# FPGA.net
KiCad netlist of a schematic drawn in Altium Designer
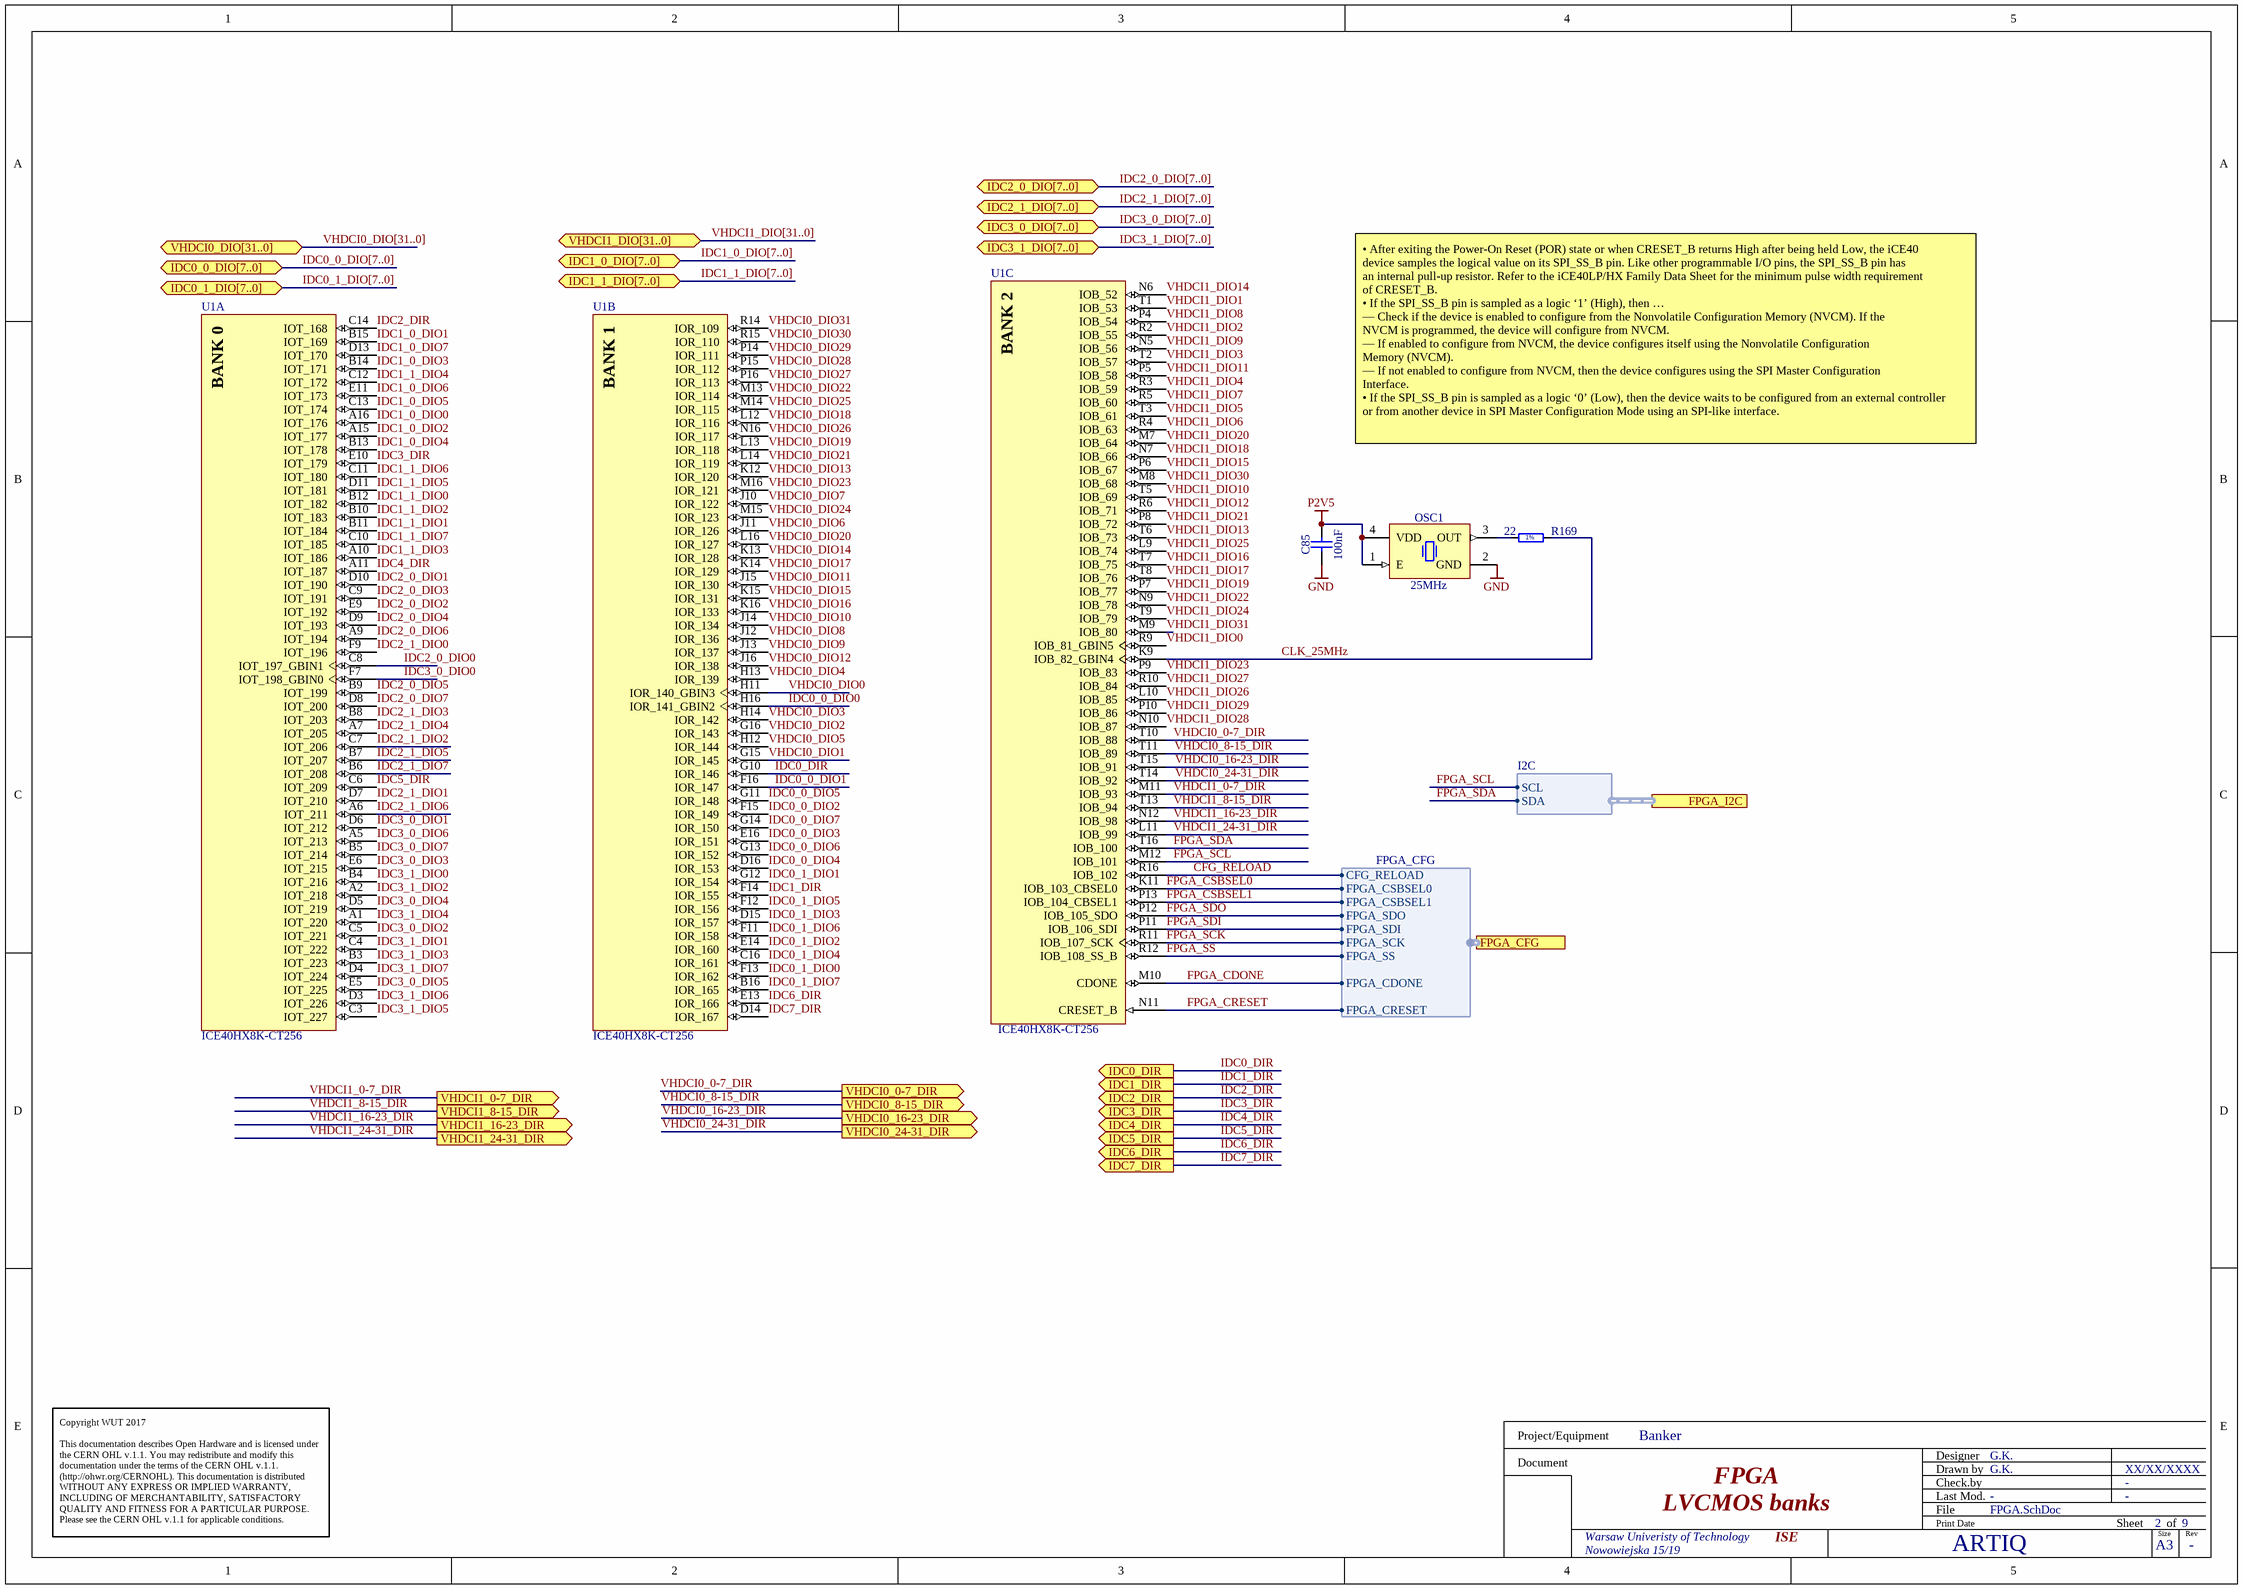
[diagram p0: FPGA.SchDoc]

(export (version "E")
  (design (tool "Eeschema 10.0.6"))
  (components
    (comp (ref "C85")
      (value "100nF")
      (footprint "CAPC1005X55N")
      (description "Non-polarised capacitor")
      (fields
        (field (name "PART NUMBER") "CC0402_100NF_16V_10%_X5R")
        (field (name "VOLTAGE") "16V")
        (field (name "AUTHOR") "CERN DEM JLC")
      )
      (libsource (lib "Capacitors") (part "Capacitor - non polarized"))
    )
    (comp (ref "OSC1")
      (value "25MHz")
      (footprint "OSC_ECS_ECS-3525")
      (description "Oscillator 4 pins 1=E/D 2=GND 3=OUT 4=VDD")
      (fields
        (field (name "PART NUMBER") "OSC_25MHZ_ECS_ECS-3525-250-B")
        (field (name "MANUFACTURER") "ECS")
        (field (name "AUTHOR") "CERN DEM JLC")
      )
      (libsource (lib "ICs And Semiconductors") (part "Oscillator 1E 2GND 3OUT 4VDD"))
    )
    (comp (ref "R169")
      (value "22")
      (footprint "RESC1005X40N")
      (description "Resistor - 1%")
      (fields
        (field (name "PART NUMBER") "R0402_22R_1%_0.0625W_100PPM")
        (field (name "POWER") "0.0625W")
        (field (name "AUTHOR") "CERN DEM JLC")
      )
      (libsource (lib "Resistors") (part "Resistor - 1%"))
    )
    (comp (ref "U1")
      (value "ICE40HX8K-CT256")
      (footprint "LATC-caBGA-256")
      (fields (field (name "MANUFACTURER") "Lattice Semiconductor"))
      (libsource (lib "Altium Content Vault") (part "LATC-HX8K-caBGA-256"))
    )
  )
  (nets
    (net (code "3") (name "/CFG_RELOAD") (class "Default")
      (node (ref "U1") (pin "R16") (pinfunction "IOB_102_R16") (pintype "bidirectional"))
    )
    (net (code "4") (name "/CLK_25MHz") (class "Default")
      (node (ref "R169") (pin "2") (pinfunction "2_2") (pintype "passive"))
      (node (ref "U1") (pin "K9") (pinfunction "IOB_82_GBIN4_K9") (pintype "bidirectional"))
    )
    (net (code "5") (name "/FPGA_CDONE") (class "Default")
      (node (ref "U1") (pin "M10") (pinfunction "CDONE_M10") (pintype "bidirectional"))
    )
    (net (code "6") (name "/FPGA_CRESET") (class "Default")
      (node (ref "U1") (pin "N11") (pinfunction "CRESET_B_N11") (pintype "input"))
    )
    (net (code "7") (name "/FPGA_CSBSEL0") (class "Default")
      (node (ref "U1") (pin "K11") (pinfunction "IOB_103_CBSEL0_K11") (pintype "bidirectional"))
    )
    (net (code "8") (name "/FPGA_CSBSEL1") (class "Default")
      (node (ref "U1") (pin "P13") (pinfunction "IOB_104_CBSEL1_P13") (pintype "bidirectional"))
    )
    (net (code "9") (name "/FPGA_SCK") (class "Default")
      (node (ref "U1") (pin "R11") (pinfunction "IOB_107_SCK_R11") (pintype "bidirectional"))
    )
    (net (code "10") (name "/FPGA_SCL") (class "Default")
      (node (ref "U1") (pin "M12") (pinfunction "IOB_101_M12") (pintype "bidirectional"))
    )
    (net (code "11") (name "/FPGA_SDA") (class "Default")
      (node (ref "U1") (pin "T16") (pinfunction "IOB_100_T16") (pintype "bidirectional"))
    )
    (net (code "12") (name "/FPGA_SDI") (class "Default")
      (node (ref "U1") (pin "P11") (pinfunction "IOB_106_SDI_P11") (pintype "bidirectional"))
    )
    (net (code "13") (name "/FPGA_SDO") (class "Default")
      (node (ref "U1") (pin "P12") (pinfunction "IOB_105_SDO_P12") (pintype "bidirectional"))
    )
    (net (code "14") (name "/FPGA_SS") (class "Default")
      (node (ref "U1") (pin "R12") (pinfunction "IOB_108_SS_B_R12") (pintype "bidirectional"))
    )
    (net (code "15") (name "/IDC0_0_DIO0") (class "Default")
      (node (ref "U1") (pin "H16") (pinfunction "IOR_141_GBIN2_H16") (pintype "bidirectional"))
    )
    (net (code "16") (name "/IDC0_0_DIO1") (class "Default")
      (node (ref "U1") (pin "F16") (pinfunction "IOR_147_F16") (pintype "bidirectional"))
    )
    (net (code "17") (name "/IDC0_0_DIO2") (class "Default")
      (node (ref "U1") (pin "F15") (pinfunction "IOR_149_F15") (pintype "bidirectional"))
    )
    (net (code "18") (name "/IDC0_0_DIO3") (class "Default")
      (node (ref "U1") (pin "E16") (pinfunction "IOR_151_E16") (pintype "bidirectional"))
    )
    (net (code "19") (name "/IDC0_0_DIO4") (class "Default")
      (node (ref "U1") (pin "D16") (pinfunction "IOR_153_D16") (pintype "bidirectional"))
    )
    (net (code "20") (name "/IDC0_0_DIO5") (class "Default")
      (node (ref "U1") (pin "G11") (pinfunction "IOR_148_G11") (pintype "bidirectional"))
    )
    (net (code "21") (name "/IDC0_0_DIO6") (class "Default")
      (node (ref "U1") (pin "G13") (pinfunction "IOR_152_G13") (pintype "bidirectional"))
    )
    (net (code "22") (name "/IDC0_0_DIO7") (class "Default")
      (node (ref "U1") (pin "G14") (pinfunction "IOR_150_G14") (pintype "bidirectional"))
    )
    (net (code "24") (name "/IDC0_1_DIO0") (class "Default")
      (node (ref "U1") (pin "F13") (pinfunction "IOR_162_F13") (pintype "bidirectional"))
    )
    (net (code "25") (name "/IDC0_1_DIO1") (class "Default")
      (node (ref "U1") (pin "G12") (pinfunction "IOR_154_G12") (pintype "bidirectional"))
    )
    (net (code "26") (name "/IDC0_1_DIO2") (class "Default")
      (node (ref "U1") (pin "E14") (pinfunction "IOR_160_E14") (pintype "bidirectional"))
    )
    (net (code "27") (name "/IDC0_1_DIO3") (class "Default")
      (node (ref "U1") (pin "D15") (pinfunction "IOR_157_D15") (pintype "bidirectional"))
    )
    (net (code "28") (name "/IDC0_1_DIO4") (class "Default")
      (node (ref "U1") (pin "C16") (pinfunction "IOR_161_C16") (pintype "bidirectional"))
    )
    (net (code "29") (name "/IDC0_1_DIO5") (class "Default")
      (node (ref "U1") (pin "F12") (pinfunction "IOR_156_F12") (pintype "bidirectional"))
    )
    (net (code "30") (name "/IDC0_1_DIO6") (class "Default")
      (node (ref "U1") (pin "F11") (pinfunction "IOR_158_F11") (pintype "bidirectional"))
    )
    (net (code "31") (name "/IDC0_1_DIO7") (class "Default")
      (node (ref "U1") (pin "B16") (pinfunction "IOR_165_B16") (pintype "bidirectional"))
    )
    (net (code "33") (name "/IDC0_DIR") (class "Default")
      (node (ref "U1") (pin "G10") (pinfunction "IOR_146_G10") (pintype "bidirectional"))
    )
    (net (code "34") (name "/IDC1_0_DIO0") (class "Default")
      (node (ref "U1") (pin "A16") (pinfunction "IOT_176_A16") (pintype "bidirectional"))
    )
    (net (code "35") (name "/IDC1_0_DIO1") (class "Default")
      (node (ref "U1") (pin "B15") (pinfunction "IOT_169_B15") (pintype "bidirectional"))
    )
    (net (code "36") (name "/IDC1_0_DIO2") (class "Default")
      (node (ref "U1") (pin "A15") (pinfunction "IOT_177_A15") (pintype "bidirectional"))
    )
    (net (code "37") (name "/IDC1_0_DIO3") (class "Default")
      (node (ref "U1") (pin "B14") (pinfunction "IOT_171_B14") (pintype "bidirectional"))
    )
    (net (code "38") (name "/IDC1_0_DIO4") (class "Default")
      (node (ref "U1") (pin "B13") (pinfunction "IOT_178_B13") (pintype "bidirectional"))
    )
    (net (code "39") (name "/IDC1_0_DIO5") (class "Default")
      (node (ref "U1") (pin "C13") (pinfunction "IOT_174_C13") (pintype "bidirectional"))
    )
    (net (code "40") (name "/IDC1_0_DIO6") (class "Default")
      (node (ref "U1") (pin "E11") (pinfunction "IOT_173_E11") (pintype "bidirectional"))
    )
    (net (code "41") (name "/IDC1_0_DIO7") (class "Default")
      (node (ref "U1") (pin "D13") (pinfunction "IOT_170_D13") (pintype "bidirectional"))
    )
    (net (code "43") (name "/IDC1_1_DIO0") (class "Default")
      (node (ref "U1") (pin "B12") (pinfunction "IOT_182_B12") (pintype "bidirectional"))
    )
    (net (code "44") (name "/IDC1_1_DIO1") (class "Default")
      (node (ref "U1") (pin "B11") (pinfunction "IOT_184_B11") (pintype "bidirectional"))
    )
    (net (code "45") (name "/IDC1_1_DIO2") (class "Default")
      (node (ref "U1") (pin "B10") (pinfunction "IOT_183_B10") (pintype "bidirectional"))
    )
    (net (code "46") (name "/IDC1_1_DIO3") (class "Default")
      (node (ref "U1") (pin "A10") (pinfunction "IOT_186_A10") (pintype "bidirectional"))
    )
    (net (code "47") (name "/IDC1_1_DIO4") (class "Default")
      (node (ref "U1") (pin "C12") (pinfunction "IOT_172_C12") (pintype "bidirectional"))
    )
    (net (code "48") (name "/IDC1_1_DIO5") (class "Default")
      (node (ref "U1") (pin "D11") (pinfunction "IOT_181_D11") (pintype "bidirectional"))
    )
    (net (code "49") (name "/IDC1_1_DIO6") (class "Default")
      (node (ref "U1") (pin "C11") (pinfunction "IOT_180_C11") (pintype "bidirectional"))
    )
    (net (code "50") (name "/IDC1_1_DIO7") (class "Default")
      (node (ref "U1") (pin "C10") (pinfunction "IOT_185_C10") (pintype "bidirectional"))
    )
    (net (code "52") (name "/IDC1_DIR") (class "Default")
      (node (ref "U1") (pin "F14") (pinfunction "IOR_155_F14") (pintype "bidirectional"))
    )
    (net (code "53") (name "/IDC2_0_DIO0") (class "Default")
      (node (ref "U1") (pin "C8") (pinfunction "IOT_197_GBIN1_C8") (pintype "bidirectional"))
    )
    (net (code "54") (name "/IDC2_0_DIO1") (class "Default")
      (node (ref "U1") (pin "D10") (pinfunction "IOT_190_D10") (pintype "bidirectional"))
    )
    (net (code "55") (name "/IDC2_0_DIO2") (class "Default")
      (node (ref "U1") (pin "E9") (pinfunction "IOT_192_E9") (pintype "bidirectional"))
    )
    (net (code "56") (name "/IDC2_0_DIO3") (class "Default")
      (node (ref "U1") (pin "C9") (pinfunction "IOT_191_C9") (pintype "bidirectional"))
    )
    (net (code "57") (name "/IDC2_0_DIO4") (class "Default")
      (node (ref "U1") (pin "D9") (pinfunction "IOT_193_D9") (pintype "bidirectional"))
    )
    (net (code "58") (name "/IDC2_0_DIO5") (class "Default")
      (node (ref "U1") (pin "B9") (pinfunction "IOT_199_B9") (pintype "bidirectional"))
    )
    (net (code "59") (name "/IDC2_0_DIO6") (class "Default")
      (node (ref "U1") (pin "A9") (pinfunction "IOT_194_A9") (pintype "bidirectional"))
    )
    (net (code "60") (name "/IDC2_0_DIO7") (class "Default")
      (node (ref "U1") (pin "D8") (pinfunction "IOT_200_D8") (pintype "bidirectional"))
    )
    (net (code "62") (name "/IDC2_1_DIO0") (class "Default")
      (node (ref "U1") (pin "F9") (pinfunction "IOT_196_F9") (pintype "bidirectional"))
    )
    (net (code "63") (name "/IDC2_1_DIO1") (class "Default")
      (node (ref "U1") (pin "D7") (pinfunction "IOT_210_D7") (pintype "bidirectional"))
    )
    (net (code "64") (name "/IDC2_1_DIO2") (class "Default")
      (node (ref "U1") (pin "C7") (pinfunction "IOT_206_C7") (pintype "bidirectional"))
    )
    (net (code "65") (name "/IDC2_1_DIO3") (class "Default")
      (node (ref "U1") (pin "B8") (pinfunction "IOT_203_B8") (pintype "bidirectional"))
    )
    (net (code "66") (name "/IDC2_1_DIO4") (class "Default")
      (node (ref "U1") (pin "A7") (pinfunction "IOT_205_A7") (pintype "bidirectional"))
    )
    (net (code "67") (name "/IDC2_1_DIO5") (class "Default")
      (node (ref "U1") (pin "B7") (pinfunction "IOT_207_B7") (pintype "bidirectional"))
    )
    (net (code "68") (name "/IDC2_1_DIO6") (class "Default")
      (node (ref "U1") (pin "A6") (pinfunction "IOT_211_A6") (pintype "bidirectional"))
    )
    (net (code "69") (name "/IDC2_1_DIO7") (class "Default")
      (node (ref "U1") (pin "B6") (pinfunction "IOT_208_B6") (pintype "bidirectional"))
    )
    (net (code "71") (name "/IDC2_DIR") (class "Default")
      (node (ref "U1") (pin "C14") (pinfunction "IOT_168_C14") (pintype "bidirectional"))
    )
    (net (code "72") (name "/IDC3_0_DIO0") (class "Default")
      (node (ref "U1") (pin "F7") (pinfunction "IOT_198_GBIN0_F7") (pintype "bidirectional"))
    )
    (net (code "73") (name "/IDC3_0_DIO1") (class "Default")
      (node (ref "U1") (pin "D6") (pinfunction "IOT_212_D6") (pintype "bidirectional"))
    )
    (net (code "74") (name "/IDC3_0_DIO2") (class "Default")
      (node (ref "U1") (pin "C5") (pinfunction "IOT_221_C5") (pintype "bidirectional"))
    )
    (net (code "75") (name "/IDC3_0_DIO3") (class "Default")
      (node (ref "U1") (pin "E6") (pinfunction "IOT_215_E6") (pintype "bidirectional"))
    )
    (net (code "76") (name "/IDC3_0_DIO4") (class "Default")
      (node (ref "U1") (pin "D5") (pinfunction "IOT_219_D5") (pintype "bidirectional"))
    )
    (net (code "77") (name "/IDC3_0_DIO5") (class "Default")
      (node (ref "U1") (pin "E5") (pinfunction "IOT_225_E5") (pintype "bidirectional"))
    )
    (net (code "78") (name "/IDC3_0_DIO6") (class "Default")
      (node (ref "U1") (pin "A5") (pinfunction "IOT_213_A5") (pintype "bidirectional"))
    )
    (net (code "79") (name "/IDC3_0_DIO7") (class "Default")
      (node (ref "U1") (pin "B5") (pinfunction "IOT_214_B5") (pintype "bidirectional"))
    )
    (net (code "81") (name "/IDC3_1_DIO0") (class "Default")
      (node (ref "U1") (pin "B4") (pinfunction "IOT_216_B4") (pintype "bidirectional"))
    )
    (net (code "82") (name "/IDC3_1_DIO1") (class "Default")
      (node (ref "U1") (pin "C4") (pinfunction "IOT_222_C4") (pintype "bidirectional"))
    )
    (net (code "83") (name "/IDC3_1_DIO2") (class "Default")
      (node (ref "U1") (pin "A2") (pinfunction "IOT_218_A2") (pintype "bidirectional"))
    )
    (net (code "84") (name "/IDC3_1_DIO3") (class "Default")
      (node (ref "U1") (pin "B3") (pinfunction "IOT_223_B3") (pintype "bidirectional"))
    )
    (net (code "85") (name "/IDC3_1_DIO4") (class "Default")
      (node (ref "U1") (pin "A1") (pinfunction "IOT_220_A1") (pintype "bidirectional"))
    )
    (net (code "86") (name "/IDC3_1_DIO5") (class "Default")
      (node (ref "U1") (pin "C3") (pinfunction "IOT_227_C3") (pintype "bidirectional"))
    )
    (net (code "87") (name "/IDC3_1_DIO6") (class "Default")
      (node (ref "U1") (pin "D3") (pinfunction "IOT_226_D3") (pintype "bidirectional"))
    )
    (net (code "88") (name "/IDC3_1_DIO7") (class "Default")
      (node (ref "U1") (pin "D4") (pinfunction "IOT_224_D4") (pintype "bidirectional"))
    )
    (net (code "90") (name "/IDC3_DIR") (class "Default")
      (node (ref "U1") (pin "E10") (pinfunction "IOT_179_E10") (pintype "bidirectional"))
    )
    (net (code "91") (name "/IDC4_DIR") (class "Default")
      (node (ref "U1") (pin "A11") (pinfunction "IOT_187_A11") (pintype "bidirectional"))
    )
    (net (code "92") (name "/IDC5_DIR") (class "Default")
      (node (ref "U1") (pin "C6") (pinfunction "IOT_209_C6") (pintype "bidirectional"))
    )
    (net (code "93") (name "/IDC6_DIR") (class "Default")
      (node (ref "U1") (pin "E13") (pinfunction "IOR_166_E13") (pintype "bidirectional"))
    )
    (net (code "94") (name "/IDC7_DIR") (class "Default")
      (node (ref "U1") (pin "D14") (pinfunction "IOR_167_D14") (pintype "bidirectional"))
    )
    (net (code "95") (name "/VHDCI0_0-7_DIR") (class "Default")
      (node (ref "U1") (pin "T10") (pinfunction "IOB_88_T10") (pintype "bidirectional"))
    )
    (net (code "96") (name "/VHDCI0_8-15_DIR") (class "Default")
      (node (ref "U1") (pin "T11") (pinfunction "IOB_89_T11") (pintype "bidirectional"))
    )
    (net (code "97") (name "/VHDCI0_16-23_DIR") (class "Default")
      (node (ref "U1") (pin "T15") (pinfunction "IOB_91_T15") (pintype "bidirectional"))
    )
    (net (code "98") (name "/VHDCI0_24-31_DIR") (class "Default")
      (node (ref "U1") (pin "T14") (pinfunction "IOB_92_T14") (pintype "bidirectional"))
    )
    (net (code "99") (name "/VHDCI0_DIO0") (class "Default")
      (node (ref "U1") (pin "H11") (pinfunction "IOR_140_GBIN3_H11") (pintype "bidirectional"))
    )
    (net (code "100") (name "/VHDCI0_DIO1") (class "Default")
      (node (ref "U1") (pin "G15") (pinfunction "IOR_145_G15") (pintype "bidirectional"))
    )
    (net (code "101") (name "/VHDCI0_DIO2") (class "Default")
      (node (ref "U1") (pin "G16") (pinfunction "IOR_143_G16") (pintype "bidirectional"))
    )
    (net (code "102") (name "/VHDCI0_DIO3") (class "Default")
      (node (ref "U1") (pin "H14") (pinfunction "IOR_142_H14") (pintype "bidirectional"))
    )
    (net (code "103") (name "/VHDCI0_DIO4") (class "Default")
      (node (ref "U1") (pin "H13") (pinfunction "IOR_139_H13") (pintype "bidirectional"))
    )
    (net (code "104") (name "/VHDCI0_DIO5") (class "Default")
      (node (ref "U1") (pin "H12") (pinfunction "IOR_144_H12") (pintype "bidirectional"))
    )
    (net (code "105") (name "/VHDCI0_DIO6") (class "Default")
      (node (ref "U1") (pin "J11") (pinfunction "IOR_126_J11") (pintype "bidirectional"))
    )
    (net (code "106") (name "/VHDCI0_DIO7") (class "Default")
      (node (ref "U1") (pin "J10") (pinfunction "IOR_122_J10") (pintype "bidirectional"))
    )
    (net (code "107") (name "/VHDCI0_DIO8") (class "Default")
      (node (ref "U1") (pin "J12") (pinfunction "IOR_136_J12") (pintype "bidirectional"))
    )
    (net (code "108") (name "/VHDCI0_DIO9") (class "Default")
      (node (ref "U1") (pin "J13") (pinfunction "IOR_137_J13") (pintype "bidirectional"))
    )
    (net (code "109") (name "/VHDCI0_DIO10") (class "Default")
      (node (ref "U1") (pin "J14") (pinfunction "IOR_134_J14") (pintype "bidirectional"))
    )
    (net (code "110") (name "/VHDCI0_DIO11") (class "Default")
      (node (ref "U1") (pin "J15") (pinfunction "IOR_130_J15") (pintype "bidirectional"))
    )
    (net (code "111") (name "/VHDCI0_DIO12") (class "Default")
      (node (ref "U1") (pin "J16") (pinfunction "IOR_138_J16") (pintype "bidirectional"))
    )
    (net (code "112") (name "/VHDCI0_DIO13") (class "Default")
      (node (ref "U1") (pin "K12") (pinfunction "IOR_120_K12") (pintype "bidirectional"))
    )
    (net (code "113") (name "/VHDCI0_DIO14") (class "Default")
      (node (ref "U1") (pin "K13") (pinfunction "IOR_128_K13") (pintype "bidirectional"))
    )
    (net (code "114") (name "/VHDCI0_DIO15") (class "Default")
      (node (ref "U1") (pin "K15") (pinfunction "IOR_131_K15") (pintype "bidirectional"))
    )
    (net (code "115") (name "/VHDCI0_DIO16") (class "Default")
      (node (ref "U1") (pin "K16") (pinfunction "IOR_133_K16") (pintype "bidirectional"))
    )
    (net (code "116") (name "/VHDCI0_DIO17") (class "Default")
      (node (ref "U1") (pin "K14") (pinfunction "IOR_129_K14") (pintype "bidirectional"))
    )
    (net (code "117") (name "/VHDCI0_DIO18") (class "Default")
      (node (ref "U1") (pin "L12") (pinfunction "IOR_116_L12") (pintype "bidirectional"))
    )
    (net (code "118") (name "/VHDCI0_DIO19") (class "Default")
      (node (ref "U1") (pin "L13") (pinfunction "IOR_118_L13") (pintype "bidirectional"))
    )
    (net (code "119") (name "/VHDCI0_DIO20") (class "Default")
      (node (ref "U1") (pin "L16") (pinfunction "IOR_127_L16") (pintype "bidirectional"))
    )
    (net (code "120") (name "/VHDCI0_DIO21") (class "Default")
      (node (ref "U1") (pin "L14") (pinfunction "IOR_119_L14") (pintype "bidirectional"))
    )
    (net (code "121") (name "/VHDCI0_DIO22") (class "Default")
      (node (ref "U1") (pin "M13") (pinfunction "IOR_114_M13") (pintype "bidirectional"))
    )
    (net (code "122") (name "/VHDCI0_DIO23") (class "Default")
      (node (ref "U1") (pin "M16") (pinfunction "IOR_121_M16") (pintype "bidirectional"))
    )
    (net (code "123") (name "/VHDCI0_DIO24") (class "Default")
      (node (ref "U1") (pin "M15") (pinfunction "IOR_123_M15") (pintype "bidirectional"))
    )
    (net (code "124") (name "/VHDCI0_DIO25") (class "Default")
      (node (ref "U1") (pin "M14") (pinfunction "IOR_115_M14") (pintype "bidirectional"))
    )
    (net (code "125") (name "/VHDCI0_DIO26") (class "Default")
      (node (ref "U1") (pin "N16") (pinfunction "IOR_117_N16") (pintype "bidirectional"))
    )
    (net (code "126") (name "/VHDCI0_DIO27") (class "Default")
      (node (ref "U1") (pin "P16") (pinfunction "IOR_113_P16") (pintype "bidirectional"))
    )
    (net (code "127") (name "/VHDCI0_DIO28") (class "Default")
      (node (ref "U1") (pin "P15") (pinfunction "IOR_112_P15") (pintype "bidirectional"))
    )
    (net (code "128") (name "/VHDCI0_DIO29") (class "Default")
      (node (ref "U1") (pin "P14") (pinfunction "IOR_111_P14") (pintype "bidirectional"))
    )
    (net (code "129") (name "/VHDCI0_DIO30") (class "Default")
      (node (ref "U1") (pin "R15") (pinfunction "IOR_110_R15") (pintype "bidirectional"))
    )
    (net (code "130") (name "/VHDCI0_DIO31") (class "Default")
      (node (ref "U1") (pin "R14") (pinfunction "IOR_109_R14") (pintype "bidirectional"))
    )
    (net (code "132") (name "/VHDCI1_0-7_DIR") (class "Default")
      (node (ref "U1") (pin "M11") (pinfunction "IOB_93_M11") (pintype "bidirectional"))
    )
    (net (code "133") (name "/VHDCI1_8-15_DIR") (class "Default")
      (node (ref "U1") (pin "T13") (pinfunction "IOB_94_T13") (pintype "bidirectional"))
    )
    (net (code "134") (name "/VHDCI1_16-23_DIR") (class "Default")
      (node (ref "U1") (pin "N12") (pinfunction "IOB_98_N12") (pintype "bidirectional"))
    )
    (net (code "135") (name "/VHDCI1_24-31_DIR") (class "Default")
      (node (ref "U1") (pin "L11") (pinfunction "IOB_99_L11") (pintype "bidirectional"))
    )
    (net (code "136") (name "/VHDCI1_DIO0") (class "Default")
      (node (ref "U1") (pin "R9") (pinfunction "IOB_81_GBIN5_R9") (pintype "bidirectional"))
    )
    (net (code "137") (name "/VHDCI1_DIO1") (class "Default")
      (node (ref "U1") (pin "T1") (pinfunction "IOB_53_T1") (pintype "bidirectional"))
    )
    (net (code "138") (name "/VHDCI1_DIO2") (class "Default")
      (node (ref "U1") (pin "R2") (pinfunction "IOB_55_R2") (pintype "bidirectional"))
    )
    (net (code "139") (name "/VHDCI1_DIO3") (class "Default")
      (node (ref "U1") (pin "T2") (pinfunction "IOB_57_T2") (pintype "bidirectional"))
    )
    (net (code "140") (name "/VHDCI1_DIO4") (class "Default")
      (node (ref "U1") (pin "R3") (pinfunction "IOB_59_R3") (pintype "bidirectional"))
    )
    (net (code "141") (name "/VHDCI1_DIO5") (class "Default")
      (node (ref "U1") (pin "T3") (pinfunction "IOB_61_T3") (pintype "bidirectional"))
    )
    (net (code "142") (name "/VHDCI1_DIO6") (class "Default")
      (node (ref "U1") (pin "R4") (pinfunction "IOB_63_R4") (pintype "bidirectional"))
    )
    (net (code "143") (name "/VHDCI1_DIO7") (class "Default")
      (node (ref "U1") (pin "R5") (pinfunction "IOB_60_R5") (pintype "bidirectional"))
    )
    (net (code "144") (name "/VHDCI1_DIO8") (class "Default")
      (node (ref "U1") (pin "P4") (pinfunction "IOB_54_P4") (pintype "bidirectional"))
    )
    (net (code "145") (name "/VHDCI1_DIO9") (class "Default")
      (node (ref "U1") (pin "N5") (pinfunction "IOB_56_N5") (pintype "bidirectional"))
    )
    (net (code "146") (name "/VHDCI1_DIO10") (class "Default")
      (node (ref "U1") (pin "T5") (pinfunction "IOB_69_T5") (pintype "bidirectional"))
    )
    (net (code "147") (name "/VHDCI1_DIO11") (class "Default")
      (node (ref "U1") (pin "P5") (pinfunction "IOB_58_P5") (pintype "bidirectional"))
    )
    (net (code "148") (name "/VHDCI1_DIO12") (class "Default")
      (node (ref "U1") (pin "R6") (pinfunction "IOB_71_R6") (pintype "bidirectional"))
    )
    (net (code "149") (name "/VHDCI1_DIO13") (class "Default")
      (node (ref "U1") (pin "T6") (pinfunction "IOB_73_T6") (pintype "bidirectional"))
    )
    (net (code "150") (name "/VHDCI1_DIO14") (class "Default")
      (node (ref "U1") (pin "N6") (pinfunction "IOB_52_N6") (pintype "bidirectional"))
    )
    (net (code "151") (name "/VHDCI1_DIO15") (class "Default")
      (node (ref "U1") (pin "P6") (pinfunction "IOB_67_P6") (pintype "bidirectional"))
    )
    (net (code "152") (name "/VHDCI1_DIO16") (class "Default")
      (node (ref "U1") (pin "T7") (pinfunction "IOB_75_T7") (pintype "bidirectional"))
    )
    (net (code "153") (name "/VHDCI1_DIO17") (class "Default")
      (node (ref "U1") (pin "T8") (pinfunction "IOB_76_T8") (pintype "bidirectional"))
    )
    (net (code "154") (name "/VHDCI1_DIO18") (class "Default")
      (node (ref "U1") (pin "N7") (pinfunction "IOB_66_N7") (pintype "bidirectional"))
    )
    (net (code "155") (name "/VHDCI1_DIO19") (class "Default")
      (node (ref "U1") (pin "P7") (pinfunction "IOB_77_P7") (pintype "bidirectional"))
    )
    (net (code "156") (name "/VHDCI1_DIO20") (class "Default")
      (node (ref "U1") (pin "M7") (pinfunction "IOB_64_M7") (pintype "bidirectional"))
    )
    (net (code "157") (name "/VHDCI1_DIO21") (class "Default")
      (node (ref "U1") (pin "P8") (pinfunction "IOB_72_P8") (pintype "bidirectional"))
    )
    (net (code "158") (name "/VHDCI1_DIO22") (class "Default")
      (node (ref "U1") (pin "N9") (pinfunction "IOB_78_N9") (pintype "bidirectional"))
    )
    (net (code "159") (name "/VHDCI1_DIO23") (class "Default")
      (node (ref "U1") (pin "P9") (pinfunction "IOB_83_P9") (pintype "bidirectional"))
    )
    (net (code "160") (name "/VHDCI1_DIO24") (class "Default")
      (node (ref "U1") (pin "T9") (pinfunction "IOB_79_T9") (pintype "bidirectional"))
    )
    (net (code "161") (name "/VHDCI1_DIO25") (class "Default")
      (node (ref "U1") (pin "L9") (pinfunction "IOB_74_L9") (pintype "bidirectional"))
    )
    (net (code "162") (name "/VHDCI1_DIO26") (class "Default")
      (node (ref "U1") (pin "L10") (pinfunction "IOB_85_L10") (pintype "bidirectional"))
    )
    (net (code "163") (name "/VHDCI1_DIO27") (class "Default")
      (node (ref "U1") (pin "R10") (pinfunction "IOB_84_R10") (pintype "bidirectional"))
    )
    (net (code "164") (name "/VHDCI1_DIO28") (class "Default")
      (node (ref "U1") (pin "N10") (pinfunction "IOB_87_N10") (pintype "bidirectional"))
    )
    (net (code "165") (name "/VHDCI1_DIO29") (class "Default")
      (node (ref "U1") (pin "P10") (pinfunction "IOB_86_P10") (pintype "bidirectional"))
    )
    (net (code "166") (name "/VHDCI1_DIO30") (class "Default")
      (node (ref "U1") (pin "M8") (pinfunction "IOB_68_M8") (pintype "bidirectional"))
    )
    (net (code "167") (name "/VHDCI1_DIO31") (class "Default")
      (node (ref "U1") (pin "M9") (pinfunction "IOB_80_M9") (pintype "bidirectional"))
    )
    (net (code "171") (name "GND") (class "Default")
      (node (ref "C85") (pin "1") (pinfunction "1_1") (pintype "passive"))
      (node (ref "OSC1") (pin "2") (pinfunction "GND_2") (pintype "power_in"))
    )
    (net (code "172") (name "Net-(OSC1-OUT)") (class "Default")
      (node (ref "OSC1") (pin "3") (pinfunction "OUT_3") (pintype "output"))
      (node (ref "R169") (pin "1") (pinfunction "1_1") (pintype "passive"))
    )
    (net (code "173") (name "P2V5") (class "Default")
      (node (ref "C85") (pin "2") (pinfunction "2_2") (pintype "passive"))
      (node (ref "OSC1") (pin "1") (pinfunction "E_1") (pintype "input"))
      (node (ref "OSC1") (pin "4") (pinfunction "VDD_4") (pintype "power_in"))
    )
  )
)
